# ADC_INPUT_FILTER.net
KiCad netlist of a schematic drawn in Altium Designer
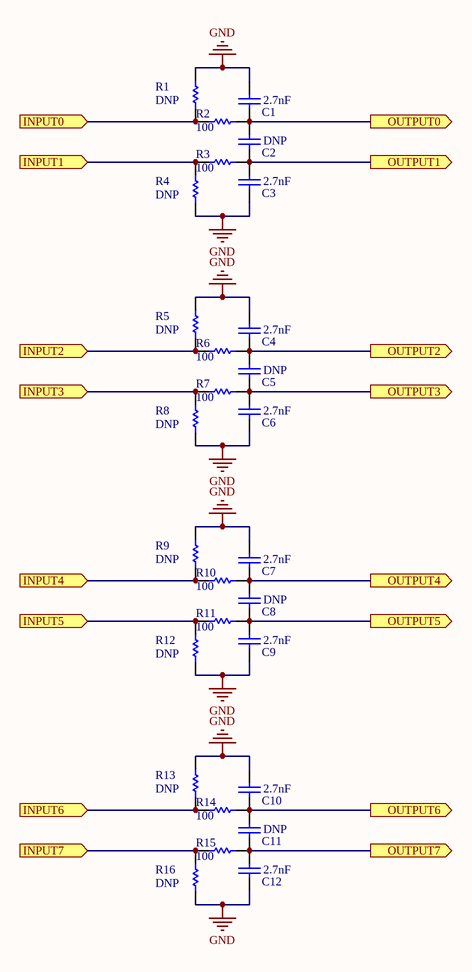
[diagram p0: ADC_INPUT_FILTER.SchDoc]

(export (version "E")
  (design (tool "Eeschema 10.0.6"))
  (components
    (comp (ref "C1")
      (value "2.7nF")
      (footprint "CAPC0402(1005)60_L")
      (description "0402 (1005 Metric) Chip Capacitor")
      (fields (field (name "Comment") "CAP0402"))
      (libsource (lib "Altium Content Vault") (part "CMP-1590-00004-1"))
    )
    (comp (ref "C2")
      (value "DNP")
      (footprint "CAPC0402(1005)60_L")
      (description "0402 (1005 Metric) Chip Capacitor")
      (fields (field (name "Comment") "CAP0402"))
      (libsource (lib "Altium Content Vault") (part "CMP-1590-00004-1"))
    )
    (comp (ref "C3")
      (value "2.7nF")
      (footprint "CAPC0402(1005)60_L")
      (description "0402 (1005 Metric) Chip Capacitor")
      (fields (field (name "Comment") "CAP0402"))
      (libsource (lib "Altium Content Vault") (part "CMP-1590-00004-1"))
    )
    (comp (ref "C4")
      (value "2.7nF")
      (footprint "CAPC0402(1005)60_L")
      (description "0402 (1005 Metric) Chip Capacitor")
      (fields (field (name "Comment") "CAP0402"))
      (libsource (lib "Altium Content Vault") (part "CMP-1590-00004-1"))
    )
    (comp (ref "C5")
      (value "DNP")
      (footprint "CAPC0402(1005)60_L")
      (description "0402 (1005 Metric) Chip Capacitor")
      (fields (field (name "Comment") "CAP0402"))
      (libsource (lib "Altium Content Vault") (part "CMP-1590-00004-1"))
    )
    (comp (ref "C6")
      (value "2.7nF")
      (footprint "CAPC0402(1005)60_L")
      (description "0402 (1005 Metric) Chip Capacitor")
      (fields (field (name "Comment") "CAP0402"))
      (libsource (lib "Altium Content Vault") (part "CMP-1590-00004-1"))
    )
    (comp (ref "C7")
      (value "2.7nF")
      (footprint "CAPC0402(1005)60_L")
      (description "0402 (1005 Metric) Chip Capacitor")
      (fields (field (name "Comment") "CAP0402"))
      (libsource (lib "Altium Content Vault") (part "CMP-1590-00004-1"))
    )
    (comp (ref "C8")
      (value "DNP")
      (footprint "CAPC0402(1005)60_L")
      (description "0402 (1005 Metric) Chip Capacitor")
      (fields (field (name "Comment") "CAP0402"))
      (libsource (lib "Altium Content Vault") (part "CMP-1590-00004-1"))
    )
    (comp (ref "C9")
      (value "2.7nF")
      (footprint "CAPC0402(1005)60_L")
      (description "0402 (1005 Metric) Chip Capacitor")
      (fields (field (name "Comment") "CAP0402"))
      (libsource (lib "Altium Content Vault") (part "CMP-1590-00004-1"))
    )
    (comp (ref "C10")
      (value "2.7nF")
      (footprint "CAPC0402(1005)60_L")
      (description "0402 (1005 Metric) Chip Capacitor")
      (fields (field (name "Comment") "CAP0402"))
      (libsource (lib "Altium Content Vault") (part "CMP-1590-00004-1"))
    )
    (comp (ref "C11")
      (value "DNP")
      (footprint "CAPC0402(1005)60_L")
      (description "0402 (1005 Metric) Chip Capacitor")
      (fields (field (name "Comment") "CAP0402"))
      (libsource (lib "Altium Content Vault") (part "CMP-1590-00004-1"))
    )
    (comp (ref "C12")
      (value "2.7nF")
      (footprint "CAPC0402(1005)60_L")
      (description "0402 (1005 Metric) Chip Capacitor")
      (fields (field (name "Comment") "CAP0402"))
      (libsource (lib "Altium Content Vault") (part "CMP-1590-00004-1"))
    )
    (comp (ref "R1")
      (value "DNP")
      (footprint "RESC0402(1005)_L")
      (description "0402 (1005 Metric) Chip Resistor")
      (fields (field (name "Comment") "RES0402"))
      (libsource (lib "Altium Content Vault") (part "CMP-1591-00004-1"))
    )
    (comp (ref "R2")
      (value "100")
      (footprint "RESC0402(1005)_L")
      (description "0402 (1005 Metric) Chip Resistor")
      (fields (field (name "Comment") "RES0402"))
      (libsource (lib "Altium Content Vault") (part "CMP-1591-00004-1"))
    )
    (comp (ref "R3")
      (value "100")
      (footprint "RESC0402(1005)_L")
      (description "0402 (1005 Metric) Chip Resistor")
      (fields (field (name "Comment") "RES0402"))
      (libsource (lib "Altium Content Vault") (part "CMP-1591-00004-1"))
    )
    (comp (ref "R4")
      (value "DNP")
      (footprint "RESC0402(1005)_L")
      (description "0402 (1005 Metric) Chip Resistor")
      (fields (field (name "Comment") "RES0402"))
      (libsource (lib "Altium Content Vault") (part "CMP-1591-00004-1"))
    )
    (comp (ref "R5")
      (value "DNP")
      (footprint "RESC0402(1005)_L")
      (description "0402 (1005 Metric) Chip Resistor")
      (fields (field (name "Comment") "RES0402"))
      (libsource (lib "Altium Content Vault") (part "CMP-1591-00004-1"))
    )
    (comp (ref "R6")
      (value "100")
      (footprint "RESC0402(1005)_L")
      (description "0402 (1005 Metric) Chip Resistor")
      (fields (field (name "Comment") "RES0402"))
      (libsource (lib "Altium Content Vault") (part "CMP-1591-00004-1"))
    )
    (comp (ref "R7")
      (value "100")
      (footprint "RESC0402(1005)_L")
      (description "0402 (1005 Metric) Chip Resistor")
      (fields (field (name "Comment") "RES0402"))
      (libsource (lib "Altium Content Vault") (part "CMP-1591-00004-1"))
    )
    (comp (ref "R8")
      (value "DNP")
      (footprint "RESC0402(1005)_L")
      (description "0402 (1005 Metric) Chip Resistor")
      (fields (field (name "Comment") "RES0402"))
      (libsource (lib "Altium Content Vault") (part "CMP-1591-00004-1"))
    )
    (comp (ref "R9")
      (value "DNP")
      (footprint "RESC0402(1005)_L")
      (description "0402 (1005 Metric) Chip Resistor")
      (fields (field (name "Comment") "RES0402"))
      (libsource (lib "Altium Content Vault") (part "CMP-1591-00004-1"))
    )
    (comp (ref "R10")
      (value "100")
      (footprint "RESC0402(1005)_L")
      (description "0402 (1005 Metric) Chip Resistor")
      (fields (field (name "Comment") "RES0402"))
      (libsource (lib "Altium Content Vault") (part "CMP-1591-00004-1"))
    )
    (comp (ref "R11")
      (value "100")
      (footprint "RESC0402(1005)_L")
      (description "0402 (1005 Metric) Chip Resistor")
      (fields (field (name "Comment") "RES0402"))
      (libsource (lib "Altium Content Vault") (part "CMP-1591-00004-1"))
    )
    (comp (ref "R12")
      (value "DNP")
      (footprint "RESC0402(1005)_L")
      (description "0402 (1005 Metric) Chip Resistor")
      (fields (field (name "Comment") "RES0402"))
      (libsource (lib "Altium Content Vault") (part "CMP-1591-00004-1"))
    )
    (comp (ref "R13")
      (value "DNP")
      (footprint "RESC0402(1005)_L")
      (description "0402 (1005 Metric) Chip Resistor")
      (fields (field (name "Comment") "RES0402"))
      (libsource (lib "Altium Content Vault") (part "CMP-1591-00004-1"))
    )
    (comp (ref "R14")
      (value "100")
      (footprint "RESC0402(1005)_L")
      (description "0402 (1005 Metric) Chip Resistor")
      (fields (field (name "Comment") "RES0402"))
      (libsource (lib "Altium Content Vault") (part "CMP-1591-00004-1"))
    )
    (comp (ref "R15")
      (value "100")
      (footprint "RESC0402(1005)_L")
      (description "0402 (1005 Metric) Chip Resistor")
      (fields (field (name "Comment") "RES0402"))
      (libsource (lib "Altium Content Vault") (part "CMP-1591-00004-1"))
    )
    (comp (ref "R16")
      (value "DNP")
      (footprint "RESC0402(1005)_L")
      (description "0402 (1005 Metric) Chip Resistor")
      (fields (field (name "Comment") "RES0402"))
      (libsource (lib "Altium Content Vault") (part "CMP-1591-00004-1"))
    )
  )
  (nets
    (net (code "1") (name "/INPUT0") (class "Default")
      (node (ref "R1") (pin "1") (pinfunction "1_1") (pintype "passive"))
      (node (ref "R2") (pin "1") (pinfunction "1_1") (pintype "passive"))
    )
    (net (code "2") (name "/INPUT1") (class "Default")
      (node (ref "R3") (pin "1") (pinfunction "1_1") (pintype "passive"))
      (node (ref "R4") (pin "2") (pinfunction "2_2") (pintype "passive"))
    )
    (net (code "3") (name "/INPUT2") (class "Default")
      (node (ref "R5") (pin "1") (pinfunction "1_1") (pintype "passive"))
      (node (ref "R6") (pin "1") (pinfunction "1_1") (pintype "passive"))
    )
    (net (code "4") (name "/INPUT3") (class "Default")
      (node (ref "R7") (pin "1") (pinfunction "1_1") (pintype "passive"))
      (node (ref "R8") (pin "2") (pinfunction "2_2") (pintype "passive"))
    )
    (net (code "5") (name "/INPUT4") (class "Default")
      (node (ref "R10") (pin "1") (pinfunction "1_1") (pintype "passive"))
      (node (ref "R9") (pin "1") (pinfunction "1_1") (pintype "passive"))
    )
    (net (code "6") (name "/INPUT5") (class "Default")
      (node (ref "R11") (pin "1") (pinfunction "1_1") (pintype "passive"))
      (node (ref "R12") (pin "2") (pinfunction "2_2") (pintype "passive"))
    )
    (net (code "7") (name "/INPUT6") (class "Default")
      (node (ref "R13") (pin "1") (pinfunction "1_1") (pintype "passive"))
      (node (ref "R14") (pin "1") (pinfunction "1_1") (pintype "passive"))
    )
    (net (code "8") (name "/INPUT7") (class "Default")
      (node (ref "R15") (pin "1") (pinfunction "1_1") (pintype "passive"))
      (node (ref "R16") (pin "2") (pinfunction "2_2") (pintype "passive"))
    )
    (net (code "9") (name "/OUTPUT0") (class "Default")
      (node (ref "C1") (pin "1") (pinfunction "1_1") (pintype "passive"))
      (node (ref "C2") (pin "2") (pinfunction "2_2") (pintype "passive"))
      (node (ref "R2") (pin "2") (pinfunction "2_2") (pintype "passive"))
    )
    (net (code "10") (name "/OUTPUT1") (class "Default")
      (node (ref "C2") (pin "1") (pinfunction "1_1") (pintype "passive"))
      (node (ref "C3") (pin "2") (pinfunction "2_2") (pintype "passive"))
      (node (ref "R3") (pin "2") (pinfunction "2_2") (pintype "passive"))
    )
    (net (code "11") (name "/OUTPUT2") (class "Default")
      (node (ref "C4") (pin "1") (pinfunction "1_1") (pintype "passive"))
      (node (ref "C5") (pin "2") (pinfunction "2_2") (pintype "passive"))
      (node (ref "R6") (pin "2") (pinfunction "2_2") (pintype "passive"))
    )
    (net (code "12") (name "/OUTPUT3") (class "Default")
      (node (ref "C5") (pin "1") (pinfunction "1_1") (pintype "passive"))
      (node (ref "C6") (pin "2") (pinfunction "2_2") (pintype "passive"))
      (node (ref "R7") (pin "2") (pinfunction "2_2") (pintype "passive"))
    )
    (net (code "13") (name "/OUTPUT4") (class "Default")
      (node (ref "C7") (pin "1") (pinfunction "1_1") (pintype "passive"))
      (node (ref "C8") (pin "2") (pinfunction "2_2") (pintype "passive"))
      (node (ref "R10") (pin "2") (pinfunction "2_2") (pintype "passive"))
    )
    (net (code "14") (name "/OUTPUT5") (class "Default")
      (node (ref "C8") (pin "1") (pinfunction "1_1") (pintype "passive"))
      (node (ref "C9") (pin "2") (pinfunction "2_2") (pintype "passive"))
      (node (ref "R11") (pin "2") (pinfunction "2_2") (pintype "passive"))
    )
    (net (code "15") (name "/OUTPUT6") (class "Default")
      (node (ref "C10") (pin "1") (pinfunction "1_1") (pintype "passive"))
      (node (ref "C11") (pin "2") (pinfunction "2_2") (pintype "passive"))
      (node (ref "R14") (pin "2") (pinfunction "2_2") (pintype "passive"))
    )
    (net (code "16") (name "/OUTPUT7") (class "Default")
      (node (ref "C11") (pin "1") (pinfunction "1_1") (pintype "passive"))
      (node (ref "C12") (pin "2") (pinfunction "2_2") (pintype "passive"))
      (node (ref "R15") (pin "2") (pinfunction "2_2") (pintype "passive"))
    )
    (net (code "17") (name "GND") (class "Default")
      (node (ref "C1") (pin "2") (pinfunction "2_2") (pintype "passive"))
      (node (ref "C10") (pin "2") (pinfunction "2_2") (pintype "passive"))
      (node (ref "C12") (pin "1") (pinfunction "1_1") (pintype "passive"))
      (node (ref "C3") (pin "1") (pinfunction "1_1") (pintype "passive"))
      (node (ref "C4") (pin "2") (pinfunction "2_2") (pintype "passive"))
      (node (ref "C6") (pin "1") (pinfunction "1_1") (pintype "passive"))
      (node (ref "C7") (pin "2") (pinfunction "2_2") (pintype "passive"))
      (node (ref "C9") (pin "1") (pinfunction "1_1") (pintype "passive"))
      (node (ref "R1") (pin "2") (pinfunction "2_2") (pintype "passive"))
      (node (ref "R12") (pin "1") (pinfunction "1_1") (pintype "passive"))
      (node (ref "R13") (pin "2") (pinfunction "2_2") (pintype "passive"))
      (node (ref "R16") (pin "1") (pinfunction "1_1") (pintype "passive"))
      (node (ref "R4") (pin "1") (pinfunction "1_1") (pintype "passive"))
      (node (ref "R5") (pin "2") (pinfunction "2_2") (pintype "passive"))
      (node (ref "R8") (pin "1") (pinfunction "1_1") (pintype "passive"))
      (node (ref "R9") (pin "2") (pinfunction "2_2") (pintype "passive"))
    )
  )
)
